# Isolation.net
KiCad netlist of a schematic drawn in Altium Designer
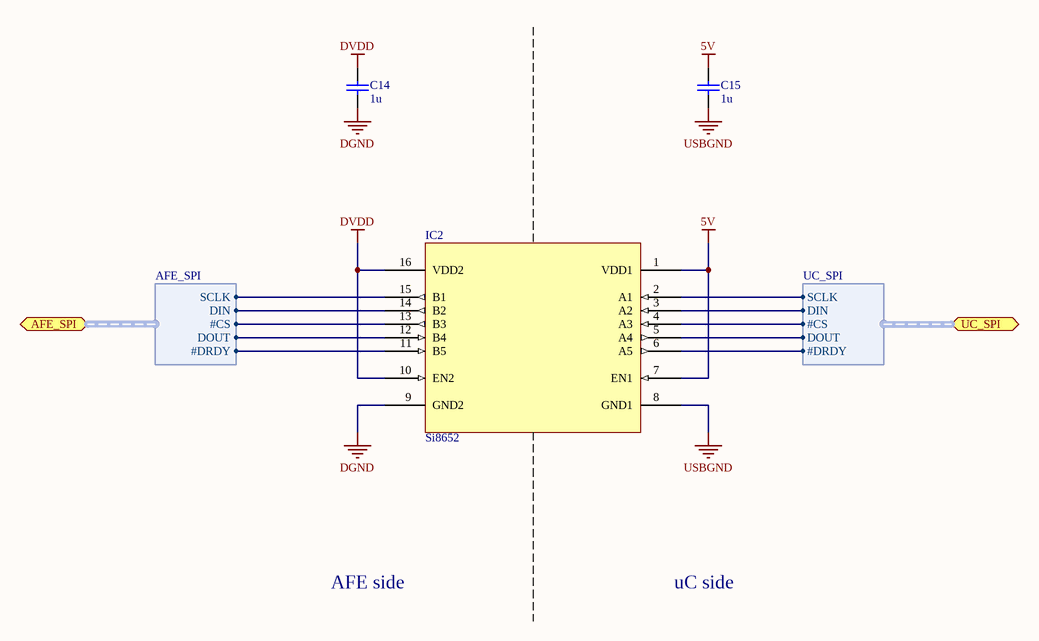
[diagram p0: Isolation.SchDoc]

(export (version "E")
  (design (tool "Eeschema 10.0.6"))
  (components
    (comp (ref "C14") (value "1u") (footprint "0805 CAP") (libsource (lib "B105lib") (part "Cap")))
    (comp (ref "C15") (value "1u") (footprint "0805 CAP") (libsource (lib "B105lib") (part "Cap")))
    (comp (ref "IC2")
      (value "Si8652")
      (footprint "SOIC127P600X175-16N")
      (libsource (lib "ECG_EMG") (part "Si8652"))
    )
  )
  (nets
    (net (code "5") (name "5V") (class "Default")
      (node (ref "C15") (pin "2") (pinfunction "2_2") (pintype "passive"))
      (node (ref "IC2") (pin "1") (pinfunction "VDD1_1") (pintype "power_in"))
      (node (ref "IC2") (pin "7") (pinfunction "EN1_7") (pintype "input"))
    )
    (net (code "6") (name "DGND") (class "Default")
      (node (ref "C14") (pin "1") (pinfunction "1_1") (pintype "passive"))
      (node (ref "IC2") (pin "9") (pinfunction "GND2_9") (pintype "power_in"))
    )
    (net (code "7") (name "DVDD") (class "Default")
      (node (ref "C14") (pin "2") (pinfunction "2_2") (pintype "passive"))
      (node (ref "IC2") (pin "10") (pinfunction "EN2_10") (pintype "input"))
      (node (ref "IC2") (pin "16") (pinfunction "VDD2_16") (pintype "power_in"))
    )
    (net (code "8") (name "USBGND") (class "Default")
      (node (ref "C15") (pin "1") (pinfunction "1_1") (pintype "passive"))
      (node (ref "IC2") (pin "8") (pinfunction "GND1_8") (pintype "power_in"))
    )
    (net (code "9") (name "unconnected-(IC2-A1-Pad2)") (class "Default")
      (node (ref "IC2") (pin "2") (pinfunction "A1_2") (pintype "input"))
    )
    (net (code "10") (name "unconnected-(IC2-A2-Pad3)") (class "Default")
      (node (ref "IC2") (pin "3") (pinfunction "A2_3") (pintype "input"))
    )
    (net (code "11") (name "unconnected-(IC2-A3-Pad4)") (class "Default")
      (node (ref "IC2") (pin "4") (pinfunction "A3_4") (pintype "input"))
    )
    (net (code "12") (name "unconnected-(IC2-A4-Pad5)") (class "Default")
      (node (ref "IC2") (pin "5") (pinfunction "A4_5") (pintype "output"))
    )
    (net (code "13") (name "unconnected-(IC2-A5-Pad6)") (class "Default")
      (node (ref "IC2") (pin "6") (pinfunction "A5_6") (pintype "output"))
    )
    (net (code "14") (name "unconnected-(IC2-B1-Pad15)") (class "Default")
      (node (ref "IC2") (pin "15") (pinfunction "B1_15") (pintype "output"))
    )
    (net (code "15") (name "unconnected-(IC2-B2-Pad14)") (class "Default")
      (node (ref "IC2") (pin "14") (pinfunction "B2_14") (pintype "output"))
    )
    (net (code "16") (name "unconnected-(IC2-B3-Pad13)") (class "Default")
      (node (ref "IC2") (pin "13") (pinfunction "B3_13") (pintype "output"))
    )
    (net (code "17") (name "unconnected-(IC2-B4-Pad12)") (class "Default")
      (node (ref "IC2") (pin "12") (pinfunction "B4_12") (pintype "input"))
    )
    (net (code "18") (name "unconnected-(IC2-B5-Pad11)") (class "Default")
      (node (ref "IC2") (pin "11") (pinfunction "B5_11") (pintype "input"))
    )
  )
)
